# LLC.net
KiCad netlist of a schematic drawn in Altium Designer
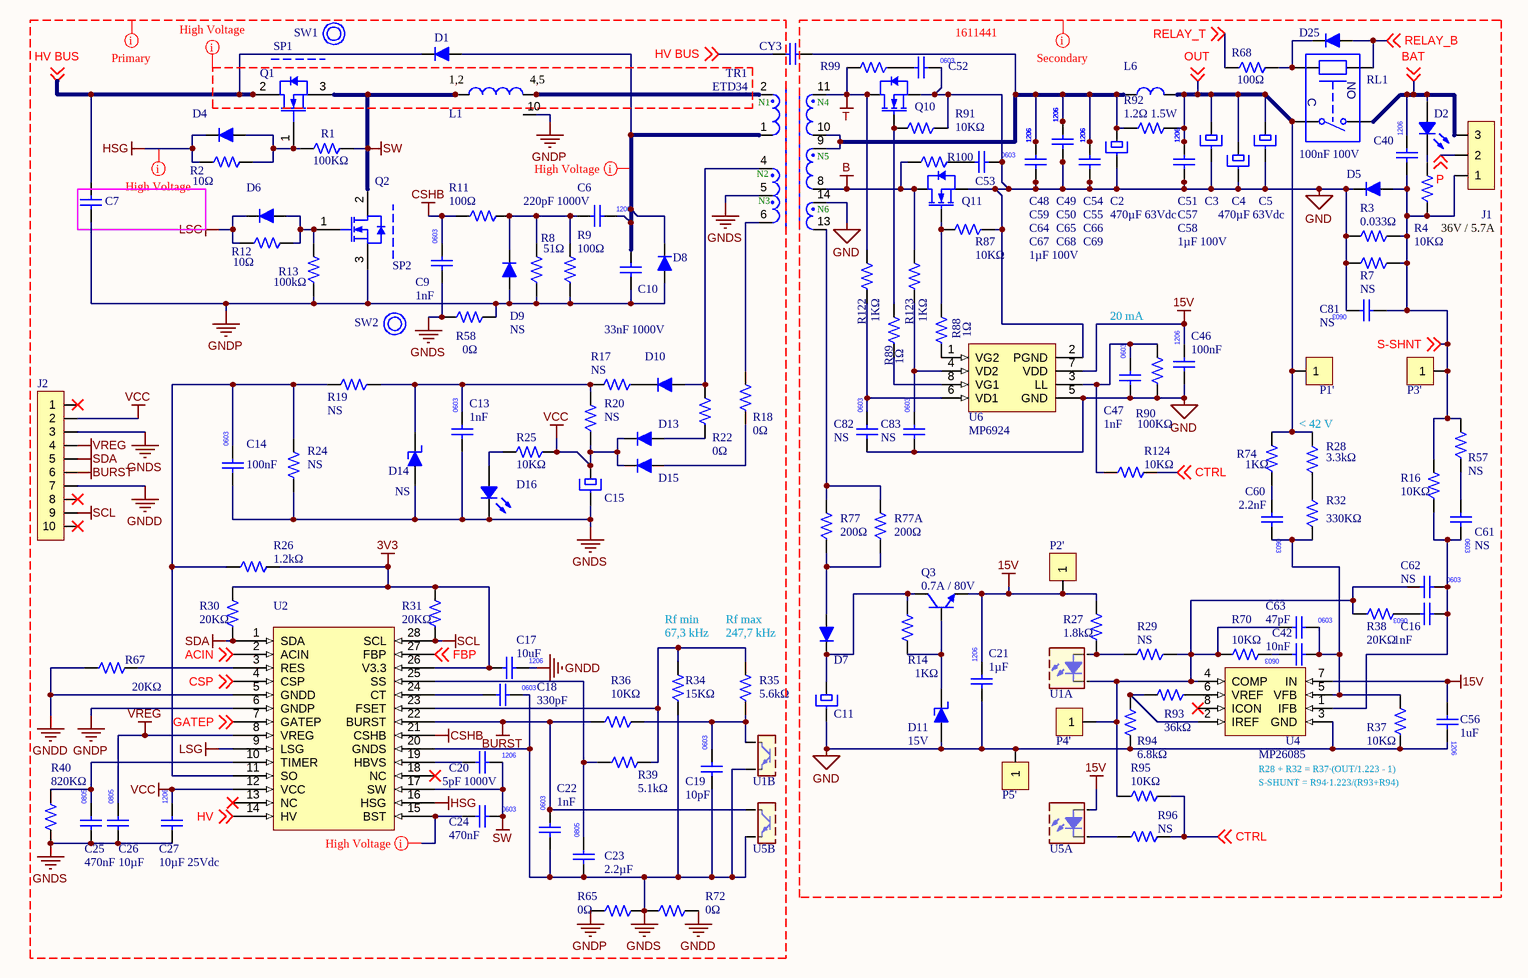
[diagram p0: LLC.SchDoc]

(export (version "E")
  (design (tool "Eeschema 10.0.6"))
  (components
    (comp (ref "C2")
      (value "470µF 63Vdc")
      (footprint "CER13x25")
      (libsource (lib "Charger") (part "Capacitor_Elec_13x25 r5"))
    )
    (comp (ref "C3")
      (value "~")
      (footprint "CER13x25")
      (libsource (lib "Charger") (part "Capacitor_Elec_13x25 r5"))
    )
    (comp (ref "C4")
      (value "~")
      (footprint "CER13x25")
      (libsource (lib "Charger") (part "Capacitor_Elec_13x25 r5"))
    )
    (comp (ref "C5")
      (value "470µF 63Vdc")
      (footprint "CER13x25")
      (libsource (lib "Charger") (part "Capacitor_Elec_13x25 r5"))
    )
    (comp (ref "C6")
      (value "220pF 1000V")
      (footprint "CC/NM 1206")
      (description "220pF")
      (libsource (lib "Capacitors_1206") (part "Capacitor 220pF"))
    )
    (comp (ref "C7")
      (value "~")
      (footprint "POL 11x20x26 r22.5")
      (libsource (lib "Charger") (part "Capacitor_26.5x10x18.5 r22.5"))
    )
    (comp (ref "C9")
      (value "1nF")
      (footprint "CC/NM 0603")
      (libsource (lib "Capacitors_0603") (part "Capacitor 220pF"))
    )
    (comp (ref "C10")
      (value "33nF 1000V")
      (footprint "17.5x8.5x15 mm")
      (libsource (lib "Charger") (part "Capacitor_17.5x8.5x15 r15mm"))
    )
    (comp (ref "C11")
      (value "~")
      (footprint "CER8x13")
      (libsource (lib "Charger") (part "Capacitor_10x13 r3.8"))
    )
    (comp (ref "C13")
      (value "1nF")
      (footprint "CC/NM 0603")
      (libsource (lib "Capacitors_0603") (part "Capacitor 1nF"))
    )
    (comp (ref "C14")
      (value "100nF")
      (footprint "CC/NM 0603")
      (libsource (lib "Capacitors_0603") (part "Capacitor 100nF"))
    )
    (comp (ref "C15")
      (value "~")
      (footprint "CER8x13")
      (libsource (lib "Charger") (part "Capacitor_10x13 r3.8"))
    )
    (comp (ref "C16")
      (value "1nF")
      (footprint "CC/NM 0603")
      (description "2.2nF")
      (libsource (lib "Capacitors_0603") (part "Capacitor 22nF"))
    )
    (comp (ref "C17")
      (value "10uF")
      (footprint "CC/NM 1206")
      (libsource (lib "Capacitors_1206") (part "Capacitor 10uF"))
    )
    (comp (ref "C18")
      (value "330pF")
      (footprint "CC/NM 0603")
      (libsource (lib "Capacitors_0603") (part "Capacitor 330pF"))
    )
    (comp (ref "C19")
      (value "10pF")
      (footprint "CC/NM 0603")
      (libsource (lib "Capacitors_0603") (part "Capacitor 10pF"))
    )
    (comp (ref "C20")
      (value "5pF 1000V")
      (footprint "CC/NM 1206")
      (description "5pF")
      (libsource (lib "Capacitors_1206") (part "Capacitor 5pF"))
    )
    (comp (ref "C21")
      (value "1µF")
      (footprint "CC/NM 1206")
      (description "1uF")
      (fields (field (name "Comment") "Capacitor 1uF"))
      (libsource (lib "Capacitors_1206") (part "Capacitor 1uF"))
    )
    (comp (ref "C22")
      (value "1nF")
      (footprint "CC/NM 0603")
      (libsource (lib "Capacitors_0603") (part "Capacitor 1nF"))
    )
    (comp (ref "C23")
      (value "2.2µF")
      (footprint "CC/NM 0805")
      (description "2.2uF")
      (libsource (lib "Capacitors_0805") (part "Capacitor 2.2uF"))
    )
    (comp (ref "C24")
      (value "470nF")
      (footprint "CC/NM 0603")
      (libsource (lib "Capacitors_0603") (part "Capacitor 330nF"))
    )
    (comp (ref "C25")
      (value "470nF")
      (footprint "CC/NM 0805")
      (libsource (lib "Capacitors_0805") (part "Capacitor 470nF"))
    )
    (comp (ref "C26")
      (value "10µF")
      (footprint "CC/NM 0805")
      (description "10uF")
      (libsource (lib "Capacitors_0805") (part "Capacitor 10uF"))
    )
    (comp (ref "C27")
      (value "10µF 25Vdc")
      (footprint "CC/NM 1206")
      (description "10uF")
      (libsource (lib "Capacitors_1206") (part "Capacitor 10uF"))
    )
    (comp (ref "C40")
      (value "100nF 100V")
      (footprint "CC/NM 1206")
      (description "1nF")
      (libsource (lib "Capacitors_1206") (part "Capacitor 1nF"))
    )
    (comp (ref "C42")
      (value "10nF")
      (footprint "CC/NM 0603")
      (libsource (lib "Capacitors_0603") (part "Capacitor 22nF"))
    )
    (comp (ref "C46")
      (value "100nF")
      (footprint "CC/NM 1206")
      (libsource (lib "Capacitors_1206") (part "Capacitor 100nF"))
    )
    (comp (ref "C47")
      (value "1nF")
      (footprint "CC/NM 0603")
      (fields (field (name "Comment") "Capacitor 1nF"))
      (libsource (lib "Capacitors_0603") (part "Capacitor 1nF"))
    )
    (comp (ref "C48")
      (value "1µF 100V")
      (footprint "CC/NM 1206")
      (description "1uF")
      (fields (field (name "VOLTAGE") "100V") (field (name "Comment") "Capacitor 1uF"))
      (libsource (lib "Capacitors_1206") (part "Capacitor 1uF"))
    )
    (comp (ref "C49")
      (value "Capacitor 1uF")
      (footprint "CC/NM 1206")
      (description "1uF")
      (fields (field (name "VOLTAGE") "100V"))
      (libsource (lib "Capacitors_1206") (part "Capacitor 1uF"))
    )
    (comp (ref "C50")
      (value "Capacitor 1uF")
      (footprint "CC/NM 1206")
      (description "1uF")
      (fields (field (name "VOLTAGE") "100V"))
      (libsource (lib "Capacitors_1206") (part "Capacitor 1uF"))
    )
    (comp (ref "C51")
      (value "Capacitor 1uF")
      (footprint "CC/NM 1206")
      (description "1uF")
      (fields (field (name "VOLTAGE") "100V"))
      (libsource (lib "Capacitors_1206") (part "Capacitor 1uF"))
    )
    (comp (ref "C52")
      (value "~")
      (footprint "CC/NM 0603")
      (description "22nF")
      (libsource (lib "Capacitors_0603") (part "Capacitor 22nF"))
    )
    (comp (ref "C53")
      (value "~")
      (footprint "CC/NM 0603")
      (description "22nF")
      (libsource (lib "Capacitors_0603") (part "Capacitor 22nF"))
    )
    (comp (ref "C54")
      (value "Capacitor 1uF")
      (footprint "CC/NM 1206")
      (description "1uF")
      (fields (field (name "VOLTAGE") "100V"))
      (libsource (lib "Capacitors_1206") (part "Capacitor 1uF"))
    )
    (comp (ref "C55")
      (value "Capacitor 1uF")
      (footprint "CC/NM 1206")
      (description "1uF")
      (fields (field (name "VOLTAGE") "100V"))
      (libsource (lib "Capacitors_1206") (part "Capacitor 1uF"))
    )
    (comp (ref "C56")
      (value "1uF")
      (footprint "CC/NM 1206")
      (fields (field (name "Comment") "Capacitor 1uF"))
      (libsource (lib "Capacitors_1206") (part "Capacitor 1uF"))
    )
    (comp (ref "C57")
      (value "Capacitor 1uF")
      (footprint "CC/NM 1206")
      (description "1uF")
      (fields (field (name "VOLTAGE") "100V"))
      (libsource (lib "Capacitors_1206") (part "Capacitor 1uF"))
    )
    (comp (ref "C58")
      (value "1µF 100V")
      (footprint "CC/NM 1206")
      (description "1uF")
      (fields (field (name "VOLTAGE") "100V") (field (name "Comment") "Capacitor 1uF"))
      (libsource (lib "Capacitors_1206") (part "Capacitor 1uF"))
    )
    (comp (ref "C59")
      (value "Capacitor 1uF")
      (footprint "CC/NM 1206")
      (description "1uF")
      (fields (field (name "VOLTAGE") "100V"))
      (libsource (lib "Capacitors_1206") (part "Capacitor 1uF"))
    )
    (comp (ref "C60")
      (value "2.2nF")
      (footprint "CC/NM 0603")
      (description "22nF")
      (libsource (lib "Capacitors_0603") (part "Capacitor 22nF"))
    )
    (comp (ref "C61")
      (value "NS")
      (footprint "CC/NM 0603")
      (description "22nF")
      (libsource (lib "Capacitors_0603") (part "Capacitor 22nF"))
    )
    (comp (ref "C62")
      (value "NS")
      (footprint "CC/NM 0603")
      (description "22nF")
      (libsource (lib "Capacitors_0603") (part "Capacitor 22nF"))
    )
    (comp (ref "C63")
      (value "47pF")
      (footprint "CC/NM 0603")
      (description "22nF")
      (libsource (lib "Capacitors_0603") (part "Capacitor 22nF"))
    )
    (comp (ref "C64")
      (value "Capacitor 1uF")
      (footprint "CC/NM 1206")
      (description "1uF")
      (fields (field (name "VOLTAGE") "100V"))
      (libsource (lib "Capacitors_1206") (part "Capacitor 1uF"))
    )
    (comp (ref "C65")
      (value "Capacitor 1uF")
      (footprint "CC/NM 1206")
      (description "1uF")
      (fields (field (name "VOLTAGE") "100V"))
      (libsource (lib "Capacitors_1206") (part "Capacitor 1uF"))
    )
    (comp (ref "C66")
      (value "Capacitor 1uF")
      (footprint "CC/NM 1206")
      (description "1uF")
      (fields (field (name "VOLTAGE") "100V"))
      (libsource (lib "Capacitors_1206") (part "Capacitor 1uF"))
    )
    (comp (ref "C67")
      (value "Capacitor 1uF")
      (footprint "CC/NM 1206")
      (description "1uF")
      (fields (field (name "VOLTAGE") "100V"))
      (libsource (lib "Capacitors_1206") (part "Capacitor 1uF"))
    )
    (comp (ref "C68")
      (value "Capacitor 1uF")
      (footprint "CC/NM 1206")
      (description "1uF")
      (fields (field (name "VOLTAGE") "100V"))
      (libsource (lib "Capacitors_1206") (part "Capacitor 1uF"))
    )
    (comp (ref "C69")
      (value "Capacitor 1uF")
      (footprint "CC/NM 1206")
      (description "1uF")
      (fields (field (name "VOLTAGE") "100V"))
      (libsource (lib "Capacitors_1206") (part "Capacitor 1uF"))
    )
    (comp (ref "C81")
      (value "NS")
      (footprint "CC/NM 0603")
      (description "1nF")
      (fields (field (name "Comment") "Capacitor 1nF"))
      (libsource (lib "Capacitors_0603") (part "Capacitor 1nF"))
    )
    (comp (ref "C82")
      (value "NS")
      (footprint "CC/NM 0603")
      (description "1nF")
      (fields (field (name "Comment") "Capacitor 1nF"))
      (libsource (lib "Capacitors_0603") (part "Capacitor 1nF"))
    )
    (comp (ref "C83")
      (value "NS")
      (footprint "CC/NM 0603")
      (description "1nF")
      (fields (field (name "Comment") "Capacitor 1nF"))
      (libsource (lib "Capacitors_0603") (part "Capacitor 1nF"))
    )
    (comp (ref "CY3")
      (value "~")
      (footprint "C_Y_r10mm")
      (libsource (lib "Charger") (part "Capacitor_Y_r10"))
    )
    (comp (ref "D1")
      (value "~")
      (footprint "DO-214AC")
      (description "Fast Rectifier 600 V, 1 A, 1.3 V, 250 ns, 30 A")
      (libsource (lib "Charger") (part "RS1J"))
    )
    (comp (ref "D2")
      (value "~")
      (footprint "LED/0603/GREEN")
      (description "LED, 0603, Green SMD, 20 mA, 2.2 V, 560 nm")
      (libsource (lib "Charger") (part "SML-D12P8WT86C"))
    )
    (comp (ref "D4")
      (value "~")
      (footprint "SODFL260X90-2N")
      (description "1N4148  miniMelf Series 500 mW 100 V Max Reverse Voltage 200 mA Small Signal Diode -")
      (libsource (lib "Charger") (part "1N4148WS"))
    )
    (comp (ref "D5") (value "~") (footprint "DO-214AC") (libsource (lib "Charger") (part "B160")))
    (comp (ref "D6")
      (value "~")
      (footprint "SODFL260X90-2N")
      (description "1N4148  miniMelf Series 500 mW 100 V Max Reverse Voltage 200 mA Small Signal Diode -")
      (libsource (lib "Charger") (part "1N4148WS"))
    )
    (comp (ref "D7") (value "~") (footprint "DO-214AC") (libsource (lib "Charger") (part "B160")))
    (comp (ref "D8")
      (value "~")
      (footprint "DO-214AC")
      (description "Fast Rectifier 600 V, 1 A, 1.3 V, 250 ns, 30 A")
      (libsource (lib "Charger") (part "RS1J"))
    )
    (comp (ref "D9")
      (value "NS")
      (footprint "SODFL260X90-2N")
      (description "1N4148  miniMelf Series 500 mW 100 V Max Reverse Voltage 200 mA Small Signal Diode -")
      (libsource (lib "Charger") (part "1N4148WS"))
    )
    (comp (ref "D10")
      (value "~")
      (footprint "SODFL260X90-2N")
      (description "1N4148  miniMelf Series 500 mW 100 V Max Reverse Voltage 200 mA Small Signal Diode -")
      (libsource (lib "Charger") (part "1N4148WS"))
    )
    (comp (ref "D11")
      (value "15V")
      (footprint "SOT95P237X112-3N")
      (libsource (lib "Charger") (part "Zener_18V"))
    )
    (comp (ref "D13") (value "~") (footprint "DO-214AC") (libsource (lib "Charger") (part "B160")))
    (comp (ref "D14")
      (value "NS")
      (footprint "SOT95P237X112-3N")
      (libsource (lib "Charger") (part "Zener_18V"))
    )
    (comp (ref "D15") (value "~") (footprint "DO-214AC") (libsource (lib "Charger") (part "B160")))
    (comp (ref "D16")
      (value "~")
      (footprint "LED/0603/GREEN")
      (description "LED, 0603, Green SMD, 20 mA, 2.2 V, 560 nm")
      (libsource (lib "Charger") (part "SML-D12P8WT86C"))
    )
    (comp (ref "D25")
      (value "~")
      (footprint "SODFL260X90-2N")
      (description "1N4148  miniMelf Series 500 mW 100 V Max Reverse Voltage 200 mA Small Signal Diode -")
      (libsource (lib "Charger") (part "1N4148WS"))
    )
    (comp (ref "J1")
      (value "MKDSN2,5/3-5.08")
      (footprint "CON 3P DIP")
      (description "CON 3p r5.08")
      (libsource (lib "Charger") (part "MKDSN2,5/3-5.08"))
    )
    (comp (ref "J2")
      (value "~")
      (footprint "Connector_10p 2.54")
      (libsource (lib "Charger") (part "Connector_COM"))
    )
    (comp (ref "L1") (value "~") (footprint "EF20 V") (libsource (lib "Charger") (part "Inductance_EF20")))
    (comp (ref "L6")
      (value "WE_744732015")
      (footprint "Ind. r5mm")
      (libsource (lib "Charger") (part "WE_744732015"))
    )
    (comp (ref "P1'") (value "PIN") (footprint "PIN") (libsource (lib "") (part "PIN_1")))
    (comp (ref "P2'") (value "PIN") (footprint "PIN") (libsource (lib "Charger") (part "PIN")))
    (comp (ref "P3'") (value "PIN") (footprint "PIN") (libsource (lib "") (part "PIN_3")))
    (comp (ref "P4'") (value "PIN") (footprint "PIN") (libsource (lib "") (part "PIN_3")))
    (comp (ref "P5'") (value "PIN") (footprint "PIN") (libsource (lib "") (part "PIN_2")))
    (comp (ref "Q1")
      (value "~")
      (footprint "TO-220 Shifted")
      (description "Transistor MOSFET, Channel N, 7.3 A, 600 V, 0.54 ohm, 10 V, 3 V")
      (libsource (lib "Charger") (part "IPP60R600C6XKSA1"))
    )
    (comp (ref "Q2")
      (value "~")
      (footprint "TO-220 Shifted")
      (description "Transistor MOSFET, Channel N, 7.3 A, 600 V, 0.54 ohm, 10 V, 3 V")
      (libsource (lib "Charger") (part "IPP60R600C6XKSA1"))
    )
    (comp (ref "Q3")
      (value "0.7A / 80V")
      (footprint "SOT89/4")
      (libsource (lib "Charger") (part "BJT_NPN_SOT89"))
    )
    (comp (ref "Q10")
      (value "NVMFS6B14NLT1G")
      (footprint "SO-8FL")
      (description "NMOS 100V 55A 19mR")
      (libsource (lib "Charger") (part "NVMFS6B14NLT1G"))
    )
    (comp (ref "Q11")
      (value "NVMFS6B14NLT1G")
      (footprint "SO-8FL")
      (description "NMOS 100V 55A 19mR")
      (libsource (lib "Charger") (part "NVMFS6B14NLT1G"))
    )
    (comp (ref "R1")
      (value "100KΩ")
      (footprint "CC/NM 0603")
      (description "Resistor 0603")
      (libsource (lib "Resistors_0603") (part "Resistor 100K"))
    )
    (comp (ref "R2")
      (value "10Ω")
      (footprint "CC/NM 0805")
      (description "Resistor 0805")
      (libsource (lib "Resistors_0805") (part "Resistor 10"))
    )
    (comp (ref "R3")
      (value "0.033Ω")
      (footprint "CC/NM 2512")
      (description "Resistor 2512")
      (libsource (lib "Resistors_2512") (part "Resistor 1"))
    )
    (comp (ref "R4")
      (value "10KΩ")
      (footprint "CC/NM 0603")
      (description "Resistor 0603")
      (libsource (lib "Resistors_0603") (part "Resistor 10K"))
    )
    (comp (ref "R7")
      (value "NS")
      (footprint "CC/NM 2512")
      (description "Resistor 2512")
      (libsource (lib "Resistors_2512") (part "Resistor 1"))
    )
    (comp (ref "R8")
      (value "51Ω")
      (footprint "CC/NM 1206")
      (description "Resistor 1206")
      (libsource (lib "Resistors_1206") (part "Resistor 51"))
    )
    (comp (ref "R9")
      (value "100Ω")
      (footprint "CC/NM 1206")
      (description "Resistor 1206")
      (libsource (lib "Resistors_1206") (part "Resistor 100"))
    )
    (comp (ref "R11")
      (value "100Ω")
      (footprint "CC/NM 0603")
      (description "Resistor 0603")
      (fields (field (name "Comment") "Resistor 100"))
      (libsource (lib "Resistors_0603") (part "Resistor 100"))
    )
    (comp (ref "R12")
      (value "10Ω")
      (footprint "CC/NM 0805")
      (description "Resistor 0805")
      (libsource (lib "Resistors_0805") (part "Resistor 10"))
    )
    (comp (ref "R13")
      (value "100kΩ")
      (footprint "CC/NM 0603")
      (description "Resistor 0603")
      (libsource (lib "Resistors_0603") (part "Resistor 100K"))
    )
    (comp (ref "R14")
      (value "1KΩ")
      (footprint "CC/NM 0603")
      (description "Resistor 0603")
      (libsource (lib "Resistors_0603") (part "Resistor 1K"))
    )
    (comp (ref "R16")
      (value "10KΩ")
      (footprint "CC/NM 0603")
      (description "Resistor 0603")
      (libsource (lib "Resistors_0603") (part "Resistor 10K"))
    )
    (comp (ref "R17")
      (value "NS")
      (footprint "CC/NM 0603")
      (description "Resistor 0603")
      (libsource (lib "Resistors_0603") (part "Resistor 0"))
    )
    (comp (ref "R18")
      (value "0Ω")
      (footprint "CC/NM 1206")
      (description "Resistor 1206")
      (libsource (lib "Resistors_1206") (part "Resistor 0"))
    )
    (comp (ref "R19")
      (value "NS")
      (footprint "CC/NM 0603")
      (description "Resistor 0603")
      (libsource (lib "Resistors_0603") (part "Resistor 0"))
    )
    (comp (ref "R20")
      (value "NS")
      (footprint "CC/NM 0603")
      (description "Resistor 0603")
      (libsource (lib "Resistors_0603") (part "Resistor 0"))
    )
    (comp (ref "R22")
      (value "0Ω")
      (footprint "CC/NM 1206")
      (description "Resistor 1206")
      (libsource (lib "Resistors_1206") (part "Resistor 0"))
    )
    (comp (ref "R24")
      (value "NS")
      (footprint "CC/NM 0603")
      (description "Resistor 0603")
      (libsource (lib "Resistors_0603") (part "Resistor 10K"))
    )
    (comp (ref "R25")
      (value "10KΩ")
      (footprint "CC/NM 0603")
      (description "Resistor 0603")
      (libsource (lib "Resistors_0603") (part "Resistor 10K"))
    )
    (comp (ref "R26")
      (value "1.2kΩ")
      (footprint "CC/NM 0603")
      (description "Resistor 0603")
      (libsource (lib "Resistors_0603") (part "Resistor 1K2"))
    )
    (comp (ref "R27")
      (value "1.8kΩ")
      (footprint "CC/NM 0603")
      (description "Resistor 0603")
      (libsource (lib "Resistors_0603") (part "Resistor 2K2"))
    )
    (comp (ref "R28")
      (value "3.3kΩ")
      (footprint "CC/NM 0603")
      (description "Resistor 0603")
      (fields (field (name "Comment") "Resistor 3K3"))
      (libsource (lib "Resistors_0603") (part "Resistor 3K3"))
    )
    (comp (ref "R29")
      (value "NS")
      (footprint "CC/NM 0603")
      (description "Resistor 0603")
      (libsource (lib "Resistors_0603") (part "Resistor 1K"))
    )
    (comp (ref "R30")
      (value "20KΩ")
      (footprint "CC/NM 0603")
      (description "Resistor 0603")
      (libsource (lib "Resistors_0603") (part "Resistor 20K"))
    )
    (comp (ref "R31")
      (value "20KΩ")
      (footprint "CC/NM 0603")
      (description "Resistor 0603")
      (libsource (lib "Resistors_0603") (part "Resistor 20K"))
    )
    (comp (ref "R32")
      (value "330KΩ")
      (footprint "CC/NM 0603")
      (description "Resistor 0603")
      (fields (field (name "Comment") "Resistor 330K"))
      (libsource (lib "Resistors_0603") (part "Resistor 330K"))
    )
    (comp (ref "R34")
      (value "15KΩ")
      (footprint "CC/NM 0603")
      (description "Resistor 0603")
      (libsource (lib "Resistors_0603") (part "Resistor 15K"))
    )
    (comp (ref "R35")
      (value "5.6kΩ")
      (footprint "CC/NM 0603")
      (description "Resistor 0603")
      (libsource (lib "Resistors_0603") (part "Resistor 5K6"))
    )
    (comp (ref "R36")
      (value "10KΩ")
      (footprint "CC/NM 0603")
      (description "Resistor 0603")
      (libsource (lib "Resistors_0603") (part "Resistor 10K"))
    )
    (comp (ref "R37")
      (value "10KΩ")
      (footprint "CC/NM 0603")
      (description "Resistor 0603")
      (libsource (lib "Resistors_0603") (part "Resistor 10K"))
    )
    (comp (ref "R38")
      (value "20KΩ")
      (footprint "CC/NM 0603")
      (description "Resistor 0603")
      (libsource (lib "Resistors_0603") (part "Resistor 20K"))
    )
    (comp (ref "R39")
      (value "5.1kΩ")
      (footprint "CC/NM 0603")
      (description "Resistor 0603")
      (libsource (lib "Resistors_0603") (part "Resistor 5K1"))
    )
    (comp (ref "R40")
      (value "820KΩ")
      (footprint "CC/NM 0603")
      (description "Resistor 0603")
      (libsource (lib "Resistors_0603") (part "Resistor 820K"))
    )
    (comp (ref "R57")
      (value "NS")
      (footprint "CC/NM 0603")
      (description "Resistor 0603")
      (libsource (lib "Resistors_0603") (part "Resistor 10K"))
    )
    (comp (ref "R58")
      (value "0Ω")
      (footprint "CC/NM 0603")
      (description "Resistor 0603")
      (libsource (lib "Resistors_0603") (part "Resistor 0"))
    )
    (comp (ref "R65")
      (value "0Ω")
      (footprint "CC/NM 0603")
      (description "Resistor 0603")
      (libsource (lib "Resistors_0603") (part "Resistor 0"))
    )
    (comp (ref "R67")
      (value "20KΩ")
      (footprint "CC/NM 0603")
      (description "Resistor 0603")
      (libsource (lib "Resistors_0603") (part "Resistor 20K"))
    )
    (comp (ref "R68")
      (value "100Ω")
      (footprint "CC/NM 1206")
      (description "Resistor 1206")
      (libsource (lib "Resistors_1206") (part "Resistor 100"))
    )
    (comp (ref "R70")
      (value "10KΩ")
      (footprint "CC/NM 0603")
      (description "Resistor 0603")
      (libsource (lib "Resistors_0603") (part "Resistor 10K"))
    )
    (comp (ref "R72")
      (value "0Ω")
      (footprint "CC/NM 0603")
      (description "Resistor 0603")
      (libsource (lib "Resistors_0603") (part "Resistor 0"))
    )
    (comp (ref "R74")
      (value "1KΩ")
      (footprint "CC/NM 0603")
      (description "Resistor 0603")
      (fields (field (name "Comment") "Resistor 1K"))
      (libsource (lib "Resistors_0603") (part "Resistor 1K"))
    )
    (comp (ref "R77")
      (value "200Ω")
      (footprint "CC/NM 1206")
      (description "Resistor 1206")
      (fields (field (name "Comment") "Resistor 0"))
      (libsource (lib "Resistors_1206") (part "Resistor 0"))
    )
    (comp (ref "R77A")
      (value "200Ω")
      (footprint "CC/NM 1206")
      (description "Resistor 1206")
      (fields (field (name "Comment") "Resistor 0"))
      (libsource (lib "Resistors_1206") (part "Resistor 0"))
    )
    (comp (ref "R87")
      (value "10KΩ")
      (footprint "CC/NM 0603")
      (description "Resistor 0603")
      (libsource (lib "Resistors_0603") (part "Resistor 10K"))
    )
    (comp (ref "R88")
      (value "1Ω")
      (footprint "CC/NM 0603")
      (description "Resistor 0603")
      (fields (field (name "Comment") "Resistor 1"))
      (libsource (lib "Resistors_0603") (part "Resistor 1"))
    )
    (comp (ref "R89")
      (value "1Ω")
      (footprint "CC/NM 0603")
      (description "Resistor 0603")
      (fields (field (name "Comment") "Resistor 1"))
      (libsource (lib "Resistors_0603") (part "Resistor 1"))
    )
    (comp (ref "R90")
      (value "100KΩ")
      (footprint "CC/NM 0603")
      (description "Resistor 0603")
      (fields (field (name "Comment") "Resistor 100K"))
      (libsource (lib "Resistors_0603") (part "Resistor 100K"))
    )
    (comp (ref "R91")
      (value "10KΩ")
      (footprint "CC/NM 0603")
      (description "Resistor 0603")
      (libsource (lib "Resistors_0603") (part "Resistor 10K"))
    )
    (comp (ref "R92")
      (value "1.2Ω 1.5W")
      (footprint "CC/NM 2512")
      (description "Resistor 2512")
      (fields (field (name "Comment") "Resistor 1"))
      (libsource (lib "Resistors_2512") (part "Resistor 1"))
    )
    (comp (ref "R93")
      (value "36kΩ")
      (footprint "CC/NM 0603")
      (description "Resistor 0603")
      (fields (field (name "Comment") "Resistor 180K"))
      (libsource (lib "Resistors_0603") (part "Resistor 180K"))
    )
    (comp (ref "R94")
      (value "6.8kΩ")
      (footprint "CC/NM 0603")
      (description "Resistor 0603")
      (fields (field (name "Comment") "Resistor 15K"))
      (libsource (lib "Resistors_0603") (part "Resistor 15K"))
    )
    (comp (ref "R95")
      (value "10KΩ")
      (footprint "CC/NM 0603")
      (description "Resistor 0603")
      (libsource (lib "Resistors_0603") (part "Resistor 10K"))
    )
    (comp (ref "R96")
      (value "NS")
      (footprint "CC/NM 0603")
      (description "Resistor 0603")
      (libsource (lib "Resistors_0603") (part "Resistor 10K"))
    )
    (comp (ref "R99")
      (value "~")
      (footprint "CC/NM 0603")
      (description "Resistor 0603")
      (libsource (lib "Resistors_0603") (part "Resistor 10K"))
    )
    (comp (ref "R100")
      (value "~")
      (footprint "CC/NM 0603")
      (description "Resistor 0603")
      (libsource (lib "Resistors_0603") (part "Resistor 10K"))
    )
    (comp (ref "R122")
      (value "1KΩ")
      (footprint "CC/NM 0603")
      (description "Resistor 0603")
      (fields (field (name "Comment") "Resistor 1K"))
      (libsource (lib "Resistors_0603") (part "Resistor 1K"))
    )
    (comp (ref "R123")
      (value "1KΩ")
      (footprint "CC/NM 0603")
      (description "Resistor 0603")
      (fields (field (name "Comment") "Resistor 1K"))
      (libsource (lib "Resistors_0603") (part "Resistor 1K"))
    )
    (comp (ref "R124")
      (value "10KΩ")
      (footprint "CC/NM 0603")
      (description "Resistor 0603")
      (libsource (lib "Resistors_0603") (part "Resistor 10K"))
    )
    (comp (ref "RL1") (value "~") (footprint "Relay 12Vdc / 10A") (libsource (lib "Charger") (part "Relay")))
    (comp (ref "SP1") (value "SIL-PAD TO-220") (libsource (lib "Charger") (part "SIL-PAD TO-220")))
    (comp (ref "SP2") (value "SIL-PAD TO-220") (libsource (lib "Charger") (part "SIL-PAD TO-220")))
    (comp (ref "SW1")
      (value "Shoulder Washer M2.5")
      (libsource (lib "Charger") (part "Shoulder Washer M2.5"))
    )
    (comp (ref "SW2")
      (value "Shoulder Washer M2.5")
      (libsource (lib "Charger") (part "Shoulder Washer M2.5"))
    )
    (comp (ref "TR1")
      (value "ETD34")
      (footprint "ETD34 V")
      (libsource (lib "Charger") (part "Transformer_ETD34"))
    )
    (comp (ref "U1") (value "~") (footprint "DIP_SMD") (libsource (lib "Charger") (part "FOD817A3SD(2)")))
    (comp (ref "U2")
      (value "~")
      (footprint "SOIC127P1030X265-28N")
      (description "High-Performance\r\nDigital PFC+LLC Combo Controller")
      (libsource (lib "Charger") (part "HR1200"))
    )
    (comp (ref "U4")
      (value "MP26085")
      (footprint "TSOP65P280X100-8N")
      (description "CC/CV Controller")
      (libsource (lib "Charger") (part "MP26085"))
    )
    (comp (ref "U5") (value "~") (footprint "DIP_SMD") (libsource (lib "Charger") (part "FOD817A3SD(2)")))
    (comp (ref "U6")
      (value "MP6924")
      (footprint "SOIC8/4.9x3.9x1.8/P1.27/L")
      (libsource (lib "Charger") (part "MP6924"))
    )
  )
  (nets
    (net (code "1") (name "3V3") (class "Default")
      (node (ref "C17") (pin "2") (pinfunction "2_2") (pintype "passive"))
      (node (ref "R26") (pin "2") (pinfunction "2_2") (pintype "passive"))
      (node (ref "R30") (pin "2") (pinfunction "2_2") (pintype "passive"))
      (node (ref "R31") (pin "2") (pinfunction "2_2") (pintype "passive"))
      (node (ref "U2") (pin "26") (pinfunction "V3.3_26") (pintype "input"))
    )
    (net (code "2") (name "15V") (class "Default")
      (node (ref "C21") (pin "1") (pinfunction "1_1") (pintype "passive"))
      (node (ref "C46") (pin "1") (pinfunction "1_1") (pintype "passive"))
      (node (ref "C56") (pin "2") (pinfunction "2_2") (pintype "passive"))
      (node (ref "P2'") (pin "1") (pinfunction "1_1") (pintype "passive"))
      (node (ref "Q3") (pin "2") (pinfunction "E_2") (pintype "passive"))
      (node (ref "R27") (pin "2") (pinfunction "2_2") (pintype "passive"))
      (node (ref "U4") (pin "7") (pinfunction "IN_7") (pintype "input"))
      (node (ref "U5") (pin "1") (pinfunction "1_1") (pintype "passive"))
      (node (ref "U6") (pin "7") (pinfunction "VDD_7") (pintype "power_in"))
    )
    (net (code "3") (name "ACIN") (class "Default")
      (node (ref "U2") (pin "2") (pinfunction "ACIN_2") (pintype "input"))
    )
    (net (code "4") (name "B") (class "Default")
      (node (ref "Q11") (pin "2") (pinfunction "DRAIN_2") (pintype "passive"))
      (node (ref "R100") (pin "2") (pinfunction "2_2") (pintype "passive"))
      (node (ref "R123") (pin "2") (pinfunction "2_2") (pintype "passive"))
      (node (ref "TR1") (pin "8") (pinfunction "8_8") (pintype "passive"))
    )
    (net (code "5") (name "BAT") (class "Default")
      (node (ref "C40") (pin "1") (pinfunction "1_1") (pintype "passive"))
      (node (ref "D2") (pin "2") (pinfunction "2_2") (pintype "passive"))
      (node (ref "J1") (pin "3") (pinfunction "3_3") (pintype "passive"))
      (node (ref "RL1") (pin "4") (pinfunction "4_4") (pintype "passive"))
    )
    (net (code "6") (name "BURST") (class "Default")
      (node (ref "C22") (pin "1") (pinfunction "1_1") (pintype "passive"))
      (node (ref "J2") (pin "6") (pinfunction "6_6") (pintype "passive"))
      (node (ref "R36") (pin "1") (pinfunction "1_1") (pintype "passive"))
      (node (ref "U2") (pin "22") (pinfunction "BURST_22") (pintype "input"))
      (node (ref "U5") (pin "4") (pinfunction "4_4") (pintype "passive"))
    )
    (net (code "7") (name "CSHB") (class "Default")
      (node (ref "C9") (pin "1") (pinfunction "1_1") (pintype "passive"))
      (node (ref "R11") (pin "1") (pinfunction "1_1") (pintype "passive"))
      (node (ref "U2") (pin "21") (pinfunction "CSHB_21") (pintype "input"))
    )
    (net (code "8") (name "CSP") (class "Default")
      (node (ref "U2") (pin "4") (pinfunction "CSP_4") (pintype "input"))
    )
    (net (code "9") (name "CTRL") (class "Default")
      (node (ref "R124") (pin "2") (pinfunction "2_2") (pintype "passive"))
      (node (ref "R95") (pin "2") (pinfunction "2_2") (pintype "passive"))
      (node (ref "R96") (pin "2") (pinfunction "2_2") (pintype "passive"))
    )
    (net (code "10") (name "FBP") (class "Default")
      (node (ref "U2") (pin "27") (pinfunction "FBP_27") (pintype "input"))
    )
    (net (code "11") (name "GATEP") (class "Default")
      (node (ref "U2") (pin "7") (pinfunction "GATEP_7") (pintype "input"))
    )
    (net (code "12") (name "GND") (class "Default")
      (node (ref "C11") (pin "2") (pinfunction "2_2") (pintype "passive"))
      (node (ref "C2") (pin "2") (pinfunction "2_2") (pintype "passive"))
      (node (ref "C21") (pin "2") (pinfunction "2_2") (pintype "passive"))
      (node (ref "C3") (pin "2") (pinfunction "2_2") (pintype "passive"))
      (node (ref "C4") (pin "2") (pinfunction "2_2") (pintype "passive"))
      (node (ref "C46") (pin "2") (pinfunction "2_2") (pintype "passive"))
      (node (ref "C47") (pin "2") (pinfunction "2_2") (pintype "passive"))
      (node (ref "C48") (pin "2") (pinfunction "2_2") (pintype "passive"))
      (node (ref "C49") (pin "2") (pinfunction "2_2") (pintype "passive"))
      (node (ref "C5") (pin "2") (pinfunction "2_2") (pintype "passive"))
      (node (ref "C50") (pin "2") (pinfunction "2_2") (pintype "passive"))
      (node (ref "C51") (pin "2") (pinfunction "2_2") (pintype "passive"))
      (node (ref "C52") (pin "1") (pinfunction "1_1") (pintype "passive"))
      (node (ref "C53") (pin "1") (pinfunction "1_1") (pintype "passive"))
      (node (ref "C54") (pin "2") (pinfunction "2_2") (pintype "passive"))
      (node (ref "C55") (pin "2") (pinfunction "2_2") (pintype "passive"))
      (node (ref "C56") (pin "1") (pinfunction "1_1") (pintype "passive"))
      (node (ref "C57") (pin "2") (pinfunction "2_2") (pintype "passive"))
      (node (ref "C58") (pin "2") (pinfunction "2_2") (pintype "passive"))
      (node (ref "C59") (pin "2") (pinfunction "2_2") (pintype "passive"))
      (node (ref "C64") (pin "2") (pinfunction "2_2") (pintype "passive"))
      (node (ref "C65") (pin "2") (pinfunction "2_2") (pintype "passive"))
      (node (ref "C66") (pin "2") (pinfunction "2_2") (pintype "passive"))
      (node (ref "C67") (pin "2") (pinfunction "2_2") (pintype "passive"))
      (node (ref "C68") (pin "2") (pinfunction "2_2") (pintype "passive"))
      (node (ref "C69") (pin "2") (pinfunction "2_2") (pintype "passive"))
      (node (ref "C81") (pin "1") (pinfunction "1_1") (pintype "passive"))
      (node (ref "C82") (pin "2") (pinfunction "2_2") (pintype "passive"))
      (node (ref "C83") (pin "2") (pinfunction "2_2") (pintype "passive"))
      (node (ref "D11") (pin "1") (pinfunction "A_1") (pintype "passive"))
      (node (ref "D5") (pin "1") (pinfunction "1_1") (pintype "passive"))
      (node (ref "P5'") (pin "1") (pinfunction "1_1") (pintype "passive"))
      (node (ref "Q10") (pin "3") (pinfunction "SOURCE_3") (pintype "passive"))
      (node (ref "Q11") (pin "3") (pinfunction "SOURCE_3") (pintype "passive"))
      (node (ref "R3") (pin "1") (pinfunction "1_1") (pintype "passive"))
      (node (ref "R37") (pin "1") (pinfunction "1_1") (pintype "passive"))
      (node (ref "R7") (pin "1") (pinfunction "1_1") (pintype "passive"))
      (node (ref "R87") (pin "1") (pinfunction "1_1") (pintype "passive"))
      (node (ref "R90") (pin "1") (pinfunction "1_1") (pintype "passive"))
      (node (ref "R91") (pin "1") (pinfunction "1_1") (pintype "passive"))
      (node (ref "R94") (pin "2") (pinfunction "2_2") (pintype "passive"))
      (node (ref "TR1") (pin "14") (pinfunction "14_14") (pintype "passive"))
      (node (ref "U4") (pin "3") (pinfunction "GND_3") (pintype "input"))
      (node (ref "U6") (pin "2") (pinfunction "PGND_2") (pintype "power_in"))
      (node (ref "U6") (pin "5") (pinfunction "GND_5") (pintype "power_in"))
    )
    (net (code "13") (name "GNDD") (class "Default")
      (node (ref "C17") (pin "1") (pinfunction "1_1") (pintype "passive"))
      (node (ref "J2") (pin "7") (pinfunction "7_7") (pintype "passive"))
      (node (ref "R67") (pin "1") (pinfunction "1_1") (pintype "passive"))
      (node (ref "R72") (pin "2") (pinfunction "2_2") (pintype "passive"))
      (node (ref "U2") (pin "5") (pinfunction "GNDD_5") (pintype "input"))
    )
    (net (code "14") (name "GNDP") (class "Default")
      (node (ref "C10") (pin "2") (pinfunction "2_2") (pintype "passive"))
      (node (ref "C7") (pin "2") (pinfunction "2_2") (pintype "passive"))
      (node (ref "D8") (pin "2") (pinfunction "2_2") (pintype "passive"))
      (node (ref "D9") (pin "2") (pinfunction "2_2") (pintype "passive"))
      (node (ref "L1") (pin "10") (pinfunction "10_10") (pintype "passive"))
      (node (ref "Q2") (pin "3") (pinfunction "SOURCE_3") (pintype "passive"))
      (node (ref "R13") (pin "1") (pinfunction "1_1") (pintype "passive"))
      (node (ref "R58") (pin "2") (pinfunction "2_2") (pintype "passive"))
      (node (ref "R65") (pin "1") (pinfunction "1_1") (pintype "passive"))
      (node (ref "R8") (pin "1") (pinfunction "1_1") (pintype "passive"))
      (node (ref "R9") (pin "1") (pinfunction "1_1") (pintype "passive"))
      (node (ref "U2") (pin "6") (pinfunction "GNDP_6") (pintype "input"))
    )
    (net (code "15") (name "GNDS") (class "Default")
      (node (ref "C13") (pin "2") (pinfunction "2_2") (pintype "passive"))
      (node (ref "C14") (pin "2") (pinfunction "2_2") (pintype "passive"))
      (node (ref "C15") (pin "2") (pinfunction "2_2") (pintype "passive"))
      (node (ref "C18") (pin "1") (pinfunction "1_1") (pintype "passive"))
      (node (ref "C19") (pin "2") (pinfunction "2_2") (pintype "passive"))
      (node (ref "C22") (pin "2") (pinfunction "2_2") (pintype "passive"))
      (node (ref "C23") (pin "2") (pinfunction "2_2") (pintype "passive"))
      (node (ref "C25") (pin "2") (pinfunction "2_2") (pintype "passive"))
      (node (ref "C26") (pin "2") (pinfunction "2_2") (pintype "passive"))
      (node (ref "C27") (pin "2") (pinfunction "2_2") (pintype "passive"))
      (node (ref "C9") (pin "2") (pinfunction "2_2") (pintype "passive"))
      (node (ref "D14") (pin "1") (pinfunction "A_1") (pintype "passive"))
      (node (ref "D16") (pin "1") (pinfunction "1_1") (pintype "passive"))
      (node (ref "J2") (pin "3") (pinfunction "3_3") (pintype "passive"))
      (node (ref "R24") (pin "1") (pinfunction "1_1") (pintype "passive"))
      (node (ref "R34") (pin "1") (pinfunction "1_1") (pintype "passive"))
      (node (ref "R40") (pin "2") (pinfunction "2_2") (pintype "passive"))
      (node (ref "R58") (pin "1") (pinfunction "1_1") (pintype "passive"))
      (node (ref "R65") (pin "2") (pinfunction "2_2") (pintype "passive"))
      (node (ref "R72") (pin "1") (pinfunction "1_1") (pintype "passive"))
      (node (ref "TR1") (pin "5") (pinfunction "5_5") (pintype "passive"))
      (node (ref "U1") (pin "3") (pinfunction "3_3") (pintype "passive"))
      (node (ref "U2") (pin "20") (pinfunction "GNDS_20") (pintype "input"))
      (node (ref "U5") (pin "3") (pinfunction "3_3") (pintype "passive"))
    )
    (net (code "16") (name "HSG") (class "Default")
      (node (ref "D4") (pin "1") (pinfunction "1_1") (pintype "passive"))
      (node (ref "R2") (pin "1") (pinfunction "1_1") (pintype "passive"))
      (node (ref "U2") (pin "16") (pinfunction "HSG_16") (pintype "input"))
    )
    (net (code "17") (name "HV") (class "Default")
      (node (ref "U2") (pin "14") (pinfunction "HV_14") (pintype "input"))
    )
    (net (code "18") (name "HV BUS") (class "Default")
      (node (ref "C7") (pin "1") (pinfunction "1_1") (pintype "passive"))
      (node (ref "CY3") (pin "1") (pinfunction "1_1") (pintype "passive"))
      (node (ref "D1") (pin "1") (pinfunction "1_1") (pintype "passive"))
      (node (ref "Q1") (pin "2") (pinfunction "DRAIN_2") (pintype "passive"))
    )
    (net (code "19") (name "LSG") (class "Default")
      (node (ref "D6") (pin "1") (pinfunction "1_1") (pintype "passive"))
      (node (ref "R12") (pin "1") (pinfunction "1_1") (pintype "passive"))
      (node (ref "U2") (pin "9") (pinfunction "LSG_9") (pintype "input"))
    )
    (net (code "20") (name "Net-(C2-Pad1)") (class "Default")
      (node (ref "C2") (pin "1") (pinfunction "1_1") (pintype "passive"))
      (node (ref "C48") (pin "1") (pinfunction "1_1") (pintype "passive"))
      (node (ref "C49") (pin "1") (pinfunction "1_1") (pintype "passive"))
      (node (ref "C50") (pin "1") (pinfunction "1_1") (pintype "passive"))
      (node (ref "C54") (pin "1") (pinfunction "1_1") (pintype "passive"))
      (node (ref "C55") (pin "1") (pinfunction "1_1") (pintype "passive"))
      (node (ref "C59") (pin "1") (pinfunction "1_1") (pintype "passive"))
      (node (ref "C64") (pin "1") (pinfunction "1_1") (pintype "passive"))
      (node (ref "C65") (pin "1") (pinfunction "1_1") (pintype "passive"))
      (node (ref "C66") (pin "1") (pinfunction "1_1") (pintype "passive"))
      (node (ref "C67") (pin "1") (pinfunction "1_1") (pintype "passive"))
      (node (ref "C68") (pin "1") (pinfunction "1_1") (pintype "passive"))
      (node (ref "C69") (pin "1") (pinfunction "1_1") (pintype "passive"))
      (node (ref "CY3") (pin "2") (pinfunction "2_2") (pintype "passive"))
      (node (ref "L6") (pin "1") (pinfunction "1_1") (pintype "passive"))
      (node (ref "R92") (pin "1") (pinfunction "1_1") (pintype "passive"))
      (node (ref "TR1") (pin "10") (pinfunction "10_10") (pintype "passive"))
      (node (ref "TR1") (pin "9") (pinfunction "9_9") (pintype "passive"))
    )
    (net (code "21") (name "Net-(C6-Pad2)") (class "Default")
      (node (ref "C6") (pin "2") (pinfunction "2_2") (pintype "passive"))
      (node (ref "D9") (pin "1") (pinfunction "1_1") (pintype "passive"))
      (node (ref "R11") (pin "2") (pinfunction "2_2") (pintype "passive"))
      (node (ref "R8") (pin "2") (pinfunction "2_2") (pintype "passive"))
      (node (ref "R9") (pin "2") (pinfunction "2_2") (pintype "passive"))
    )
    (net (code "22") (name "Net-(C10-Pad1)") (class "Default")
      (node (ref "C10") (pin "1") (pinfunction "1_1") (pintype "passive"))
      (node (ref "C6") (pin "1") (pinfunction "1_1") (pintype "passive"))
      (node (ref "D1") (pin "2") (pinfunction "2_2") (pintype "passive"))
      (node (ref "D8") (pin "1") (pinfunction "1_1") (pintype "passive"))
      (node (ref "TR1") (pin "1") (pinfunction "1_1") (pintype "passive"))
    )
    (net (code "23") (name "Net-(C16-Pad1)") (class "Default")
      (node (ref "C16") (pin "1") (pinfunction "1_1") (pintype "passive"))
      (node (ref "R38") (pin "2") (pinfunction "2_2") (pintype "passive"))
    )
    (net (code "24") (name "Net-(C19-Pad1)") (class "Default")
      (node (ref "C19") (pin "1") (pinfunction "1_1") (pintype "passive"))
      (node (ref "R35") (pin "1") (pinfunction "1_1") (pintype "passive"))
      (node (ref "R36") (pin "2") (pinfunction "2_2") (pintype "passive"))
      (node (ref "U1") (pin "4") (pinfunction "4_4") (pintype "passive"))
    )
    (net (code "25") (name "Net-(C42-Pad1)") (class "Default")
      (node (ref "C42") (pin "1") (pinfunction "1_1") (pintype "passive"))
      (node (ref "R70") (pin "2") (pinfunction "2_2") (pintype "passive"))
    )
    (net (code "26") (name "Net-(C52-Pad2)") (class "Default")
      (node (ref "C52") (pin "2") (pinfunction "2_2") (pintype "passive"))
      (node (ref "R99") (pin "1") (pinfunction "1_1") (pintype "passive"))
    )
    (net (code "27") (name "Net-(C53-Pad2)") (class "Default")
      (node (ref "C53") (pin "2") (pinfunction "2_2") (pintype "passive"))
      (node (ref "R100") (pin "1") (pinfunction "1_1") (pintype "passive"))
    )
    (net (code "28") (name "Net-(C60-Pad2)") (class "Default")
      (node (ref "C60") (pin "2") (pinfunction "2_2") (pintype "passive"))
      (node (ref "R74") (pin "1") (pinfunction "1_1") (pintype "passive"))
    )
    (net (code "29") (name "Net-(C61-Pad2)") (class "Default")
      (node (ref "C61") (pin "2") (pinfunction "2_2") (pintype "passive"))
      (node (ref "R57") (pin "1") (pinfunction "1_1") (pintype "passive"))
    )
    (net (code "30") (name "Net-(D2-Pad1)") (class "Default")
      (node (ref "D2") (pin "1") (pinfunction "1_1") (pintype "passive"))
      (node (ref "R4") (pin "2") (pinfunction "2_2") (pintype "passive"))
    )
    (net (code "31") (name "Net-(D7-Pad2)") (class "Default")
      (node (ref "D7") (pin "2") (pinfunction "2_2") (pintype "passive"))
      (node (ref "R77") (pin "1") (pinfunction "1_1") (pintype "passive"))
      (node (ref "R77A") (pin "1") (pinfunction "1_1") (pintype "passive"))
    )
    (net (code "32") (name "Net-(D10-Pad1)") (class "Default")
      (node (ref "D10") (pin "1") (pinfunction "1_1") (pintype "passive"))
      (node (ref "R17") (pin "1") (pinfunction "1_1") (pintype "passive"))
    )
    (net (code "33") (name "Net-(D11-K)") (class "Default")
      (node (ref "D11") (pin "3") (pinfunction "K_3") (pintype "passive"))
      (node (ref "Q3") (pin "1") (pinfunction "B_1") (pintype "passive"))
      (node (ref "R14") (pin "2") (pinfunction "2_2") (pintype "passive"))
    )
    (net (code "34") (name "Net-(D13-Pad2)") (class "Default")
      (node (ref "D13") (pin "2") (pinfunction "2_2") (pintype "passive"))
      (node (ref "R22") (pin "1") (pinfunction "1_1") (pintype "passive"))
    )
    (net (code "35") (name "Net-(D14-K)") (class "Default")
      (node (ref "C13") (pin "1") (pinfunction "1_1") (pintype "passive"))
      (node (ref "D14") (pin "3") (pinfunction "K_3") (pintype "passive"))
      (node (ref "R17") (pin "2") (pinfunction "2_2") (pintype "passive"))
      (node (ref "R19") (pin "1") (pinfunction "1_1") (pintype "passive"))
      (node (ref "R20") (pin "2") (pinfunction "2_2") (pintype "passive"))
    )
    (net (code "36") (name "Net-(D15-Pad2)") (class "Default")
      (node (ref "D15") (pin "2") (pinfunction "2_2") (pintype "passive"))
      (node (ref "R18") (pin "1") (pinfunction "1_1") (pintype "passive"))
    )
    (net (code "37") (name "Net-(D16-Pad2)") (class "Default")
      (node (ref "D16") (pin "2") (pinfunction "2_2") (pintype "passive"))
      (node (ref "R25") (pin "2") (pinfunction "2_2") (pintype "passive"))
    )
    (net (code "38") (name "Net-(D25-Pad1)") (class "Default")
      (node (ref "D25") (pin "1") (pinfunction "1_1") (pintype "passive"))
      (node (ref "R68") (pin "2") (pinfunction "2_2") (pintype "passive"))
      (node (ref "RL1") (pin "1") (pinfunction "1_1") (pintype "passive"))
    )
    (net (code "39") (name "Net-(L1-Pad4)") (class "Default")
      (node (ref "L1") (pin "4") (pinfunction "4_4") (pintype "passive"))
      (node (ref "L1") (pin "5") (pinfunction "5_5") (pintype "passive"))
      (node (ref "TR1") (pin "2") (pinfunction "2_2") (pintype "passive"))
    )
    (net (code "40") (name "Net-(Q1-GATE)") (class "Default")
      (node (ref "D4") (pin "2") (pinfunction "2_2") (pintype "passive"))
      (node (ref "Q1") (pin "1") (pinfunction "GATE_1") (pintype "passive"))
      (node (ref "R1") (pin "2") (pinfunction "2_2") (pintype "passive"))
      (node (ref "R2") (pin "2") (pinfunction "2_2") (pintype "passive"))
    )
    (net (code "41") (name "Net-(Q2-GATE)") (class "Default")
      (node (ref "D6") (pin "2") (pinfunction "2_2") (pintype "passive"))
      (node (ref "Q2") (pin "1") (pinfunction "GATE_1") (pintype "passive"))
      (node (ref "R12") (pin "2") (pinfunction "2_2") (pintype "passive"))
      (node (ref "R13") (pin "2") (pinfunction "2_2") (pintype "passive"))
    )
    (net (code "42") (name "Net-(Q3-C)") (class "Default")
      (node (ref "C11") (pin "1") (pinfunction "1_1") (pintype "passive"))
      (node (ref "D7") (pin "1") (pinfunction "1_1") (pintype "passive"))
      (node (ref "Q3") (pin "3") (pinfunction "C_3") (pintype "passive"))
      (node (ref "R14") (pin "1") (pinfunction "1_1") (pintype "passive"))
    )
    (net (code "43") (name "Net-(Q10-GATE)") (class "Default")
      (node (ref "Q10") (pin "1") (pinfunction "GATE_1") (pintype "passive"))
      (node (ref "R89") (pin "2") (pinfunction "2_2") (pintype "passive"))
      (node (ref "R91") (pin "2") (pinfunction "2_2") (pintype "passive"))
    )
    (net (code "44") (name "Net-(Q11-GATE)") (class "Default")
      (node (ref "Q11") (pin "1") (pinfunction "GATE_1") (pintype "passive"))
      (node (ref "R87") (pin "2") (pinfunction "2_2") (pintype "passive"))
      (node (ref "R88") (pin "2") (pinfunction "2_2") (pintype "passive"))
    )
    (net (code "45") (name "Net-(R18-Pad2)") (class "Default")
      (node (ref "R18") (pin "2") (pinfunction "2_2") (pintype "passive"))
      (node (ref "TR1") (pin "6") (pinfunction "6_6") (pintype "passive"))
    )
    (net (code "46") (name "Net-(R27-Pad1)") (class "Default")
      (node (ref "R27") (pin "1") (pinfunction "1_1") (pintype "passive"))
      (node (ref "R29") (pin "2") (pinfunction "2_2") (pintype "passive"))
      (node (ref "U1") (pin "1") (pinfunction "1_1") (pintype "passive"))
    )
    (net (code "47") (name "Net-(R28-Pad2)") (class "Default")
      (node (ref "R28") (pin "2") (pinfunction "2_2") (pintype "passive"))
      (node (ref "R32") (pin "1") (pinfunction "1_1") (pintype "passive"))
    )
    (net (code "48") (name "Net-(R77-Pad2)") (class "Default")
      (node (ref "R77") (pin "2") (pinfunction "2_2") (pintype "passive"))
      (node (ref "R77A") (pin "2") (pinfunction "2_2") (pintype "passive"))
      (node (ref "TR1") (pin "13") (pinfunction "13_13") (pintype "passive"))
    )
    (net (code "49") (name "Net-(R96-Pad1)") (class "Default")
      (node (ref "R96") (pin "1") (pinfunction "1_1") (pintype "passive"))
      (node (ref "U5") (pin "2") (pinfunction "2_2") (pintype "passive"))
    )
    (net (code "50") (name "Net-(TR1-3)") (class "Default")
      (node (ref "D10") (pin "2") (pinfunction "2_2") (pintype "passive"))
      (node (ref "R22") (pin "2") (pinfunction "2_2") (pintype "passive"))
      (node (ref "TR1") (pin "4") (pinfunction "3_4") (pintype "passive"))
    )
    (net (code "51") (name "Net-(U2-BST)") (class "Default")
      (node (ref "C24") (pin "2") (pinfunction "2_2") (pintype "passive"))
      (node (ref "U2") (pin "15") (pinfunction "BST_15") (pintype "input"))
    )
    (net (code "52") (name "Net-(U2-CT)") (class "Default")
      (node (ref "C18") (pin "2") (pinfunction "2_2") (pintype "passive"))
      (node (ref "U2") (pin "24") (pinfunction "CT_24") (pintype "input"))
    )
    (net (code "53") (name "Net-(U2-FSET)") (class "Default")
      (node (ref "R34") (pin "2") (pinfunction "2_2") (pintype "passive"))
      (node (ref "R35") (pin "2") (pinfunction "2_2") (pintype "passive"))
      (node (ref "R39") (pin "2") (pinfunction "2_2") (pintype "passive"))
      (node (ref "U2") (pin "23") (pinfunction "FSET_23") (pintype "input"))
    )
    (net (code "54") (name "Net-(U2-HBVS)") (class "Default")
      (node (ref "C20") (pin "2") (pinfunction "2_2") (pintype "passive"))
      (node (ref "U2") (pin "19") (pinfunction "HBVS_19") (pintype "input"))
    )
    (net (code "55") (name "Net-(U2-RES)") (class "Default")
      (node (ref "R67") (pin "2") (pinfunction "2_2") (pintype "passive"))
      (node (ref "U2") (pin "3") (pinfunction "RES_3") (pintype "input"))
    )
    (net (code "56") (name "Net-(U2-SO)") (class "Default")
      (node (ref "C14") (pin "1") (pinfunction "1_1") (pintype "passive"))
      (node (ref "R19") (pin "2") (pinfunction "2_2") (pintype "passive"))
      (node (ref "R24") (pin "2") (pinfunction "2_2") (pintype "passive"))
      (node (ref "R26") (pin "1") (pinfunction "1_1") (pintype "passive"))
      (node (ref "U2") (pin "11") (pinfunction "SO_11") (pintype "input"))
    )
    (net (code "57") (name "Net-(U2-SS)") (class "Default")
      (node (ref "C23") (pin "1") (pinfunction "1_1") (pintype "passive"))
      (node (ref "R39") (pin "1") (pinfunction "1_1") (pintype "passive"))
      (node (ref "U2") (pin "25") (pinfunction "SS_25") (pintype "input"))
    )
    (net (code "58") (name "Net-(U2-TIMER)") (class "Default")
      (node (ref "C25") (pin "1") (pinfunction "1_1") (pintype "passive"))
      (node (ref "R40") (pin "1") (pinfunction "1_1") (pintype "passive"))
      (node (ref "U2") (pin "10") (pinfunction "TIMER_10") (pintype "input"))
    )
    (net (code "59") (name "Net-(U4-COMP)") (class "Default")
      (node (ref "C62") (pin "2") (pinfunction "2_2") (pintype "passive"))
      (node (ref "C63") (pin "2") (pinfunction "2_2") (pintype "passive"))
      (node (ref "P4'") (pin "1") (pinfunction "1_1") (pintype "passive"))
      (node (ref "R29") (pin "1") (pinfunction "1_1") (pintype "passive"))
      (node (ref "R38") (pin "1") (pinfunction "1_1") (pintype "passive"))
      (node (ref "R70") (pin "1") (pinfunction "1_1") (pintype "passive"))
      (node (ref "R95") (pin "1") (pinfunction "1_1") (pintype "passive"))
      (node (ref "U1") (pin "2") (pinfunction "2_2") (pintype "passive"))
      (node (ref "U4") (pin "4") (pinfunction "COMP_4") (pintype "input"))
    )
    (net (code "60") (name "Net-(U4-IFB)") (class "Default")
      (node (ref "C16") (pin "2") (pinfunction "2_2") (pintype "passive"))
      (node (ref "C61") (pin "1") (pinfunction "1_1") (pintype "passive"))
      (node (ref "C62") (pin "1") (pinfunction "1_1") (pintype "passive"))
      (node (ref "R16") (pin "1") (pinfunction "1_1") (pintype "passive"))
      (node (ref "U4") (pin "1") (pinfunction "IFB_1") (pintype "input"))
    )
    (net (code "61") (name "Net-(U4-IREF)") (class "Default")
      (node (ref "R93") (pin "2") (pinfunction "2_2") (pintype "passive"))
      (node (ref "R94") (pin "1") (pinfunction "1_1") (pintype "passive"))
      (node (ref "U4") (pin "2") (pinfunction "IREF_2") (pintype "input"))
    )
    (net (code "62") (name "Net-(U4-VFB)") (class "Default")
      (node (ref "C42") (pin "2") (pinfunction "2_2") (pintype "passive"))
      (node (ref "C60") (pin "1") (pinfunction "1_1") (pintype "passive"))
      (node (ref "C63") (pin "1") (pinfunction "1_1") (pintype "passive"))
      (node (ref "R32") (pin "2") (pinfunction "2_2") (pintype "passive"))
      (node (ref "R37") (pin "2") (pinfunction "2_2") (pintype "passive"))
      (node (ref "U4") (pin "5") (pinfunction "VFB_5") (pintype "input"))
    )
    (net (code "63") (name "Net-(U4-VREF)") (class "Default")
      (node (ref "R93") (pin "1") (pinfunction "1_1") (pintype "passive"))
      (node (ref "U4") (pin "6") (pinfunction "VREF_6") (pintype "input"))
    )
    (net (code "64") (name "Net-(U6-LL)") (class "Default")
      (node (ref "C47") (pin "1") (pinfunction "1_1") (pintype "passive"))
      (node (ref "R124") (pin "1") (pinfunction "1_1") (pintype "passive"))
      (node (ref "R90") (pin "2") (pinfunction "2_2") (pintype "passive"))
      (node (ref "U6") (pin "3") (pinfunction "LL_3") (pintype "passive"))
    )
    (net (code "65") (name "Net-(U6-VD1)") (class "Default")
      (node (ref "C82") (pin "1") (pinfunction "1_1") (pintype "passive"))
      (node (ref "R122") (pin "1") (pinfunction "1_1") (pintype "passive"))
      (node (ref "U6") (pin "6") (pinfunction "VD1_6") (pintype "input"))
    )
    (net (code "66") (name "Net-(U6-VD2)") (class "Default")
      (node (ref "C83") (pin "1") (pinfunction "1_1") (pintype "passive"))
      (node (ref "R123") (pin "1") (pinfunction "1_1") (pintype "passive"))
      (node (ref "U6") (pin "4") (pinfunction "VD2_4") (pintype "input"))
    )
    (net (code "67") (name "Net-(U6-VG1)") (class "Default")
      (node (ref "R89") (pin "1") (pinfunction "1_1") (pintype "passive"))
      (node (ref "U6") (pin "8") (pinfunction "VG1_8") (pintype "input"))
    )
    (net (code "68") (name "Net-(U6-VG2)") (class "Default")
      (node (ref "R88") (pin "1") (pinfunction "1_1") (pintype "passive"))
      (node (ref "U6") (pin "1") (pinfunction "VG2_1") (pintype "input"))
    )
    (net (code "69") (name "OUT") (class "Default")
      (node (ref "C3") (pin "1") (pinfunction "1_1") (pintype "passive"))
      (node (ref "C4") (pin "1") (pinfunction "1_1") (pintype "passive"))
      (node (ref "C5") (pin "1") (pinfunction "1_1") (pintype "passive"))
      (node (ref "C51") (pin "1") (pinfunction "1_1") (pintype "passive"))
      (node (ref "C57") (pin "1") (pinfunction "1_1") (pintype "passive"))
      (node (ref "C58") (pin "1") (pinfunction "1_1") (pintype "passive"))
      (node (ref "L6") (pin "2") (pinfunction "2_2") (pintype "passive"))
      (node (ref "P1'") (pin "1") (pinfunction "1_1") (pintype "passive"))
      (node (ref "R28") (pin "1") (pinfunction "1_1") (pintype "passive"))
      (node (ref "R74") (pin "2") (pinfunction "2_2") (pintype "passive"))
      (node (ref "R92") (pin "2") (pinfunction "2_2") (pintype "passive"))
      (node (ref "RL1") (pin "3") (pinfunction "3_3") (pintype "passive"))
    )
    (net (code "70") (name "P") (class "Default")
      (node (ref "J1") (pin "2") (pinfunction "2_2") (pintype "passive"))
    )
    (net (code "71") (name "RELAY_B") (class "Default")
      (node (ref "D25") (pin "2") (pinfunction "2_2") (pintype "passive"))
      (node (ref "RL1") (pin "2") (pinfunction "2_2") (pintype "passive"))
    )
    (net (code "72") (name "RELAY_T") (class "Default")
      (node (ref "R68") (pin "1") (pinfunction "1_1") (pintype "passive"))
    )
    (net (code "73") (name "S-SHNT") (class "Default")
      (node (ref "C40") (pin "2") (pinfunction "2_2") (pintype "passive"))
      (node (ref "C81") (pin "2") (pinfunction "2_2") (pintype "passive"))
      (node (ref "D5") (pin "2") (pinfunction "2_2") (pintype "passive"))
      (node (ref "J1") (pin "1") (pinfunction "1_1") (pintype "passive"))
      (node (ref "P3'") (pin "1") (pinfunction "1_1") (pintype "passive"))
      (node (ref "R16") (pin "2") (pinfunction "2_2") (pintype "passive"))
      (node (ref "R3") (pin "2") (pinfunction "2_2") (pintype "passive"))
      (node (ref "R4") (pin "1") (pinfunction "1_1") (pintype "passive"))
      (node (ref "R57") (pin "2") (pinfunction "2_2") (pintype "passive"))
      (node (ref "R7") (pin "2") (pinfunction "2_2") (pintype "passive"))
    )
    (net (code "74") (name "SCL") (class "Default")
      (node (ref "J2") (pin "9") (pinfunction "9_9") (pintype "passive"))
      (node (ref "R31") (pin "1") (pinfunction "1_1") (pintype "passive"))
      (node (ref "U2") (pin "28") (pinfunction "SCL_28") (pintype "input"))
    )
    (net (code "75") (name "SDA") (class "Default")
      (node (ref "J2") (pin "5") (pinfunction "5_5") (pintype "passive"))
      (node (ref "R30") (pin "1") (pinfunction "1_1") (pintype "passive"))
      (node (ref "U2") (pin "1") (pinfunction "SDA_1") (pintype "input"))
    )
    (net (code "76") (name "SW") (class "Default")
      (node (ref "C20") (pin "1") (pinfunction "1_1") (pintype "passive"))
      (node (ref "C24") (pin "1") (pinfunction "1_1") (pintype "passive"))
      (node (ref "L1") (pin "1") (pinfunction "1_1") (pintype "passive"))
      (node (ref "L1") (pin "2") (pinfunction "2_2") (pintype "passive"))
      (node (ref "Q1") (pin "3") (pinfunction "SOURCE_3") (pintype "passive"))
      (node (ref "Q2") (pin "2") (pinfunction "DRAIN_2") (pintype "passive"))
      (node (ref "R1") (pin "1") (pinfunction "1_1") (pintype "passive"))
      (node (ref "U2") (pin "17") (pinfunction "SW_17") (pintype "input"))
    )
    (net (code "77") (name "T") (class "Default")
      (node (ref "Q10") (pin "2") (pinfunction "DRAIN_2") (pintype "passive"))
      (node (ref "R122") (pin "2") (pinfunction "2_2") (pintype "passive"))
      (node (ref "R99") (pin "2") (pinfunction "2_2") (pintype "passive"))
      (node (ref "TR1") (pin "11") (pinfunction "11_11") (pintype "passive"))
    )
    (net (code "78") (name "VCC") (class "Default")
      (node (ref "C15") (pin "1") (pinfunction "1_1") (pintype "passive"))
      (node (ref "C27") (pin "1") (pinfunction "1_1") (pintype "passive"))
      (node (ref "D13") (pin "1") (pinfunction "1_1") (pintype "passive"))
      (node (ref "D15") (pin "1") (pinfunction "1_1") (pintype "passive"))
      (node (ref "J2") (pin "2") (pinfunction "2_2") (pintype "passive"))
      (node (ref "R20") (pin "1") (pinfunction "1_1") (pintype "passive"))
      (node (ref "R25") (pin "1") (pinfunction "1_1") (pintype "passive"))
      (node (ref "U2") (pin "12") (pinfunction "VCC_12") (pintype "input"))
    )
    (net (code "79") (name "VREG") (class "Default")
      (node (ref "C26") (pin "1") (pinfunction "1_1") (pintype "passive"))
      (node (ref "J2") (pin "4") (pinfunction "4_4") (pintype "passive"))
      (node (ref "U2") (pin "8") (pinfunction "VREG_8") (pintype "input"))
    )
    (net (code "80") (name "unconnected-(J2-Pad1)") (class "Default")
      (node (ref "J2") (pin "1") (pinfunction "1_1") (pintype "passive+no_connect"))
    )
    (net (code "81") (name "unconnected-(J2-Pad8)") (class "Default")
      (node (ref "J2") (pin "8") (pinfunction "8_8") (pintype "passive+no_connect"))
    )
    (net (code "82") (name "unconnected-(J2-Pad10)") (class "Default")
      (node (ref "J2") (pin "10") (pinfunction "10_10") (pintype "passive+no_connect"))
    )
    (net (code "83") (name "unconnected-(U2-NC-Pad13)") (class "Default")
      (node (ref "U2") (pin "13") (pinfunction "NC_13") (pintype "input+no_connect"))
    )
    (net (code "84") (name "unconnected-(U2-NC-Pad18)") (class "Default")
      (node (ref "U2") (pin "18") (pinfunction "NC_18") (pintype "input+no_connect"))
    )
    (net (code "85") (name "unconnected-(U4-ICON-Pad8)") (class "Default")
      (node (ref "U4") (pin "8") (pinfunction "ICON_8") (pintype "input+no_connect"))
    )
  )
)
